# Europroto2.net
KiCad netlist of a schematic drawn in EAGLE
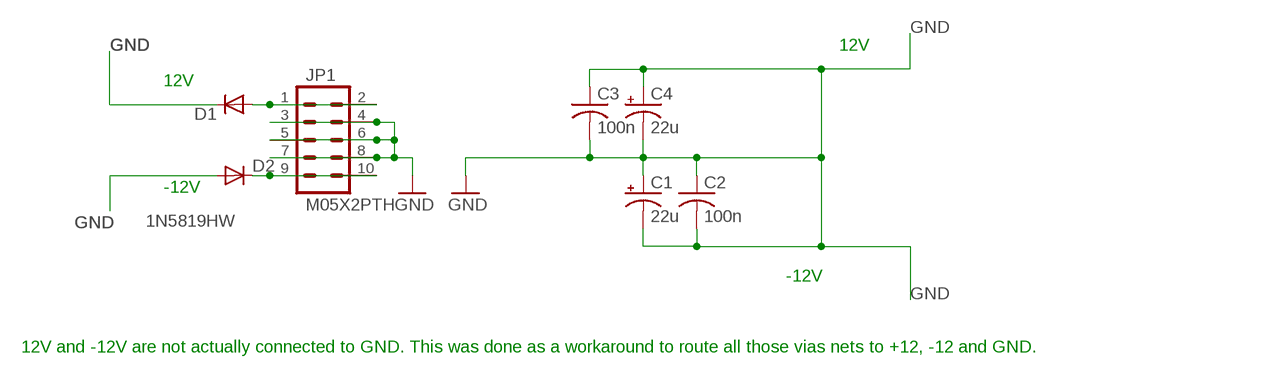
[diagram p0: schematic, sheet 1]

(export (version "E")
  (design (tool "Eeschema 10.0.6"))
  (components
    (comp (ref "C1")
      (value "22u")
      (footprint "eagle-import:PANASONIC_B")
      (libsource (lib "eagle-import") (part "CPOL-USB"))
    )
    (comp (ref "C2")
      (value "100n")
      (footprint "eagle-import:C0603")
      (libsource (lib "eagle-import") (part "C-USC0603"))
    )
    (comp (ref "C3")
      (value "100n")
      (footprint "eagle-import:C0603")
      (libsource (lib "eagle-import") (part "C-USC0603"))
    )
    (comp (ref "C4")
      (value "22u")
      (footprint "eagle-import:PANASONIC_B")
      (libsource (lib "eagle-import") (part "CPOL-USB"))
    )
    (comp (ref "D1")
      (value "1N5819HW")
      (footprint "eagle-import:SOD123")
      (libsource (lib "eagle-import") (part "DIODE-SOD123"))
    )
    (comp (ref "D2")
      (value "1N5819HW")
      (footprint "eagle-import:SOD123")
      (libsource (lib "eagle-import") (part "DIODE-SOD123"))
    )
    (comp (ref "JP1")
      (value "M05X2PTH")
      (footprint "eagle-import:AVR_ICSP")
      (libsource (lib "eagle-import") (part "M05X2PTH"))
    )
  )
  (nets
    (net (code "1") (name "GND") (class "Default")
      (node (ref "C1") (pin "+") (pinfunction "+_+") (pintype "passive"))
      (node (ref "C1") (pin "-") (pinfunction "-_-") (pintype "passive"))
      (node (ref "C2") (pin "1") (pinfunction "1_1") (pintype "passive"))
      (node (ref "C2") (pin "2") (pinfunction "2_2") (pintype "passive"))
      (node (ref "C3") (pin "1") (pinfunction "1_1") (pintype "passive"))
      (node (ref "C3") (pin "2") (pinfunction "2_2") (pintype "passive"))
      (node (ref "C4") (pin "+") (pinfunction "+_+") (pintype "passive"))
      (node (ref "C4") (pin "-") (pinfunction "-_-") (pintype "passive"))
      (node (ref "D1") (pin "C") (pinfunction "C_C") (pintype "passive"))
      (node (ref "D2") (pin "A") (pinfunction "A_A") (pintype "passive"))
      (node (ref "JP1") (pin "3") (pinfunction "3_3") (pintype "passive"))
      (node (ref "JP1") (pin "4") (pinfunction "4_4") (pintype "passive"))
      (node (ref "JP1") (pin "5") (pinfunction "5_5") (pintype "passive"))
      (node (ref "JP1") (pin "6") (pinfunction "6_6") (pintype "passive"))
      (node (ref "JP1") (pin "7") (pinfunction "7_7") (pintype "passive"))
      (node (ref "JP1") (pin "8") (pinfunction "8_8") (pintype "passive"))
    )
    (net (code "2") (name "Net-(D1-PadA)") (class "Default")
      (node (ref "D1") (pin "A") (pinfunction "A_A") (pintype "passive"))
      (node (ref "JP1") (pin "1") (pinfunction "1_1") (pintype "passive"))
      (node (ref "JP1") (pin "2") (pinfunction "2_2") (pintype "passive"))
    )
    (net (code "3") (name "Net-(D2-PadC)") (class "Default")
      (node (ref "D2") (pin "C") (pinfunction "C_C") (pintype "passive"))
      (node (ref "JP1") (pin "10") (pinfunction "10_10") (pintype "passive"))
      (node (ref "JP1") (pin "9") (pinfunction "9_9") (pintype "passive"))
    )
  )
)
